# Transmit_module.net
KiCad netlist of a schematic drawn in EAGLE
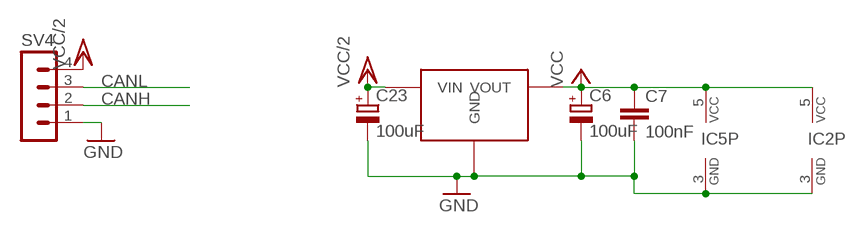
[diagram p0: schematic, sheet 1]
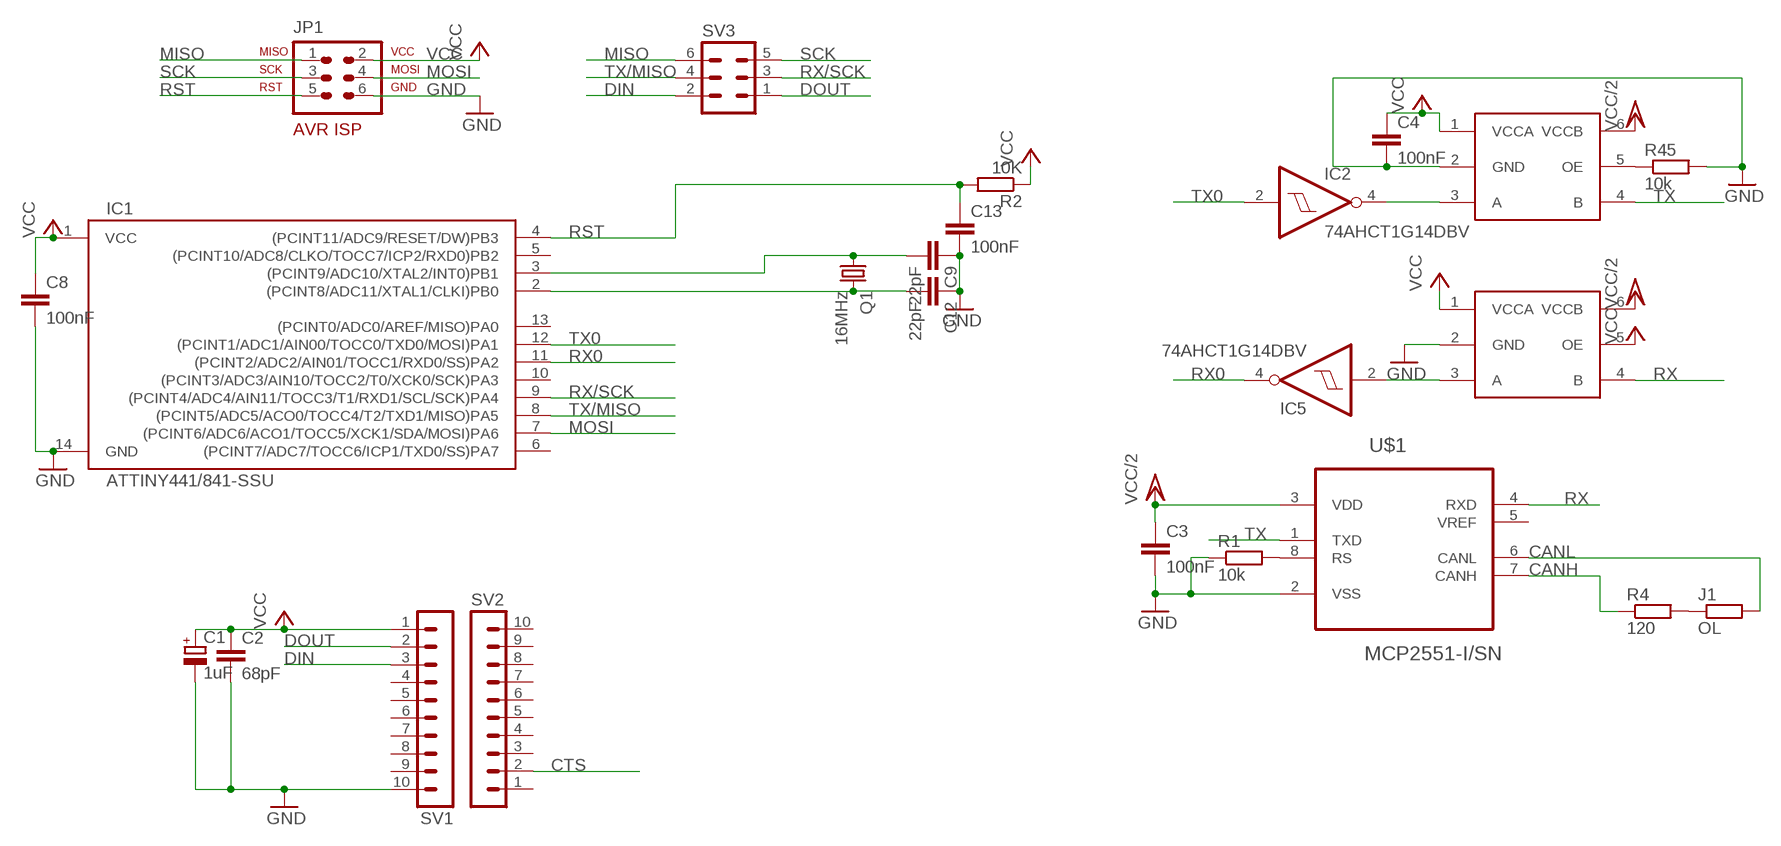
[diagram p1: schematic, sheet 2]

(export (version "E")
  (design (tool "Eeschema 10.0.6"))
  (components
    (comp (ref "C6")
      (value "100uF")
      (footprint "eagle-import:153CLV-0605")
      (libsource (lib "eagle-import") (part "CPOL-EU153CLV-0605"))
    )
    (comp (ref "C7")
      (value "100nF")
      (footprint "eagle-import:C0805")
      (libsource (lib "eagle-import") (part "C-EUC0805"))
    )
    (comp (ref "C23")
      (value "100uF")
      (footprint "eagle-import:153CLV-0605")
      (libsource (lib "eagle-import") (part "CPOL-EU153CLV-0605"))
    )
    (comp (ref "IC2")
      (value "74AHCT1G14DBV")
      (footprint "eagle-import:SOT23-5")
      (libsource (lib "eagle-import") (part "741G14DBVAHCT"))
    )
    (comp (ref "IC5")
      (value "74AHCT1G14DBV")
      (footprint "eagle-import:SOT23-5")
      (libsource (lib "eagle-import") (part "741G14DBVAHCT"))
    )
    (comp (ref "SV4")
      (value "MA04-1")
      (footprint "eagle-import:MA04-1")
      (libsource (lib "eagle-import") (part "MA04-1"))
    )
    (comp (ref "U$2")
      (value "TS2940")
      (footprint "eagle-import:TO-252")
      (libsource (lib "eagle-import") (part "TS2940"))
    )
    (comp (ref "C1")
      (value "1uF")
      (footprint "eagle-import:153CLV-0505")
      (libsource (lib "eagle-import") (part "CPOL-EU153CLV-0505"))
    )
    (comp (ref "C2")
      (value "68pF")
      (footprint "eagle-import:C0805")
      (libsource (lib "eagle-import") (part "C-EUC0805"))
    )
    (comp (ref "C3")
      (value "100nF")
      (footprint "eagle-import:C0805")
      (libsource (lib "eagle-import") (part "C-EUC0805"))
    )
    (comp (ref "C4")
      (value "100nF")
      (footprint "eagle-import:C0805")
      (libsource (lib "eagle-import") (part "C-EUC0805"))
    )
    (comp (ref "C8")
      (value "100nF")
      (footprint "eagle-import:C0805")
      (libsource (lib "eagle-import") (part "C-EUC0805"))
    )
    (comp (ref "C9")
      (value "22pF")
      (footprint "eagle-import:C0805")
      (libsource (lib "eagle-import") (part "C-EUC0805"))
    )
    (comp (ref "C12")
      (value "22pF")
      (footprint "eagle-import:C0805")
      (libsource (lib "eagle-import") (part "C-EUC0805"))
    )
    (comp (ref "C13")
      (value "100nF")
      (footprint "eagle-import:C0805")
      (libsource (lib "eagle-import") (part "C-EUC0805"))
    )
    (comp (ref "IC1")
      (value "ATTINY441/841-SSU")
      (footprint "eagle-import:SOIC14N")
      (libsource (lib "eagle-import") (part "ATTINY441/841-SSU"))
    )
    (comp (ref "J1")
      (value "OL")
      (footprint "eagle-import:R0805")
      (libsource (lib "eagle-import") (part "R-EU_R0805"))
    )
    (comp (ref "JP1")
      (value "AVR-ISP-6VERT")
      (footprint "eagle-import:AVR-ISP-6")
      (libsource (lib "eagle-import") (part "AVR-ISP-6VERT"))
    )
    (comp (ref "Q1")
      (value "16MHz")
      (footprint "eagle-import:HC49UP")
      (libsource (lib "eagle-import") (part "CRYSTALHC49UP"))
    )
    (comp (ref "R1")
      (value "10k")
      (footprint "eagle-import:M0805")
      (libsource (lib "eagle-import") (part "resistor_R-EU_M0805"))
    )
    (comp (ref "R2")
      (value "10K")
      (footprint "eagle-import:R0805")
      (libsource (lib "eagle-import") (part "R-EU_R0805"))
    )
    (comp (ref "R4")
      (value "120")
      (footprint "eagle-import:R0805")
      (libsource (lib "eagle-import") (part "R-EU_R0805"))
    )
    (comp (ref "R45")
      (value "10k")
      (footprint "eagle-import:R0805")
      (libsource (lib "eagle-import") (part "R-EU_R0805"))
    )
    (comp (ref "SV1")
      (value "MA10-1")
      (footprint "eagle-import:MA10-1")
      (libsource (lib "eagle-import") (part "MA10-1"))
    )
    (comp (ref "SV2")
      (value "MA10-1")
      (footprint "eagle-import:MA10-1")
      (libsource (lib "eagle-import") (part "MA10-1"))
    )
    (comp (ref "SV3")
      (value "MA03-2")
      (footprint "eagle-import:MA03-2")
      (libsource (lib "eagle-import") (part "MA03-2"))
    )
    (comp (ref "U$1")
      (value "MCP2551-I/SN")
      (footprint "eagle-import:SOIC127P600X175-8N")
      (libsource (lib "eagle-import") (part "MCP2551-I/SN"))
    )
    (comp (ref "U$3")
      (value "TXB0101")
      (footprint "eagle-import:TSOT23-6_DDC")
      (libsource (lib "eagle-import") (part "TXB0101"))
    )
    (comp (ref "U$4")
      (value "TXB0101")
      (footprint "eagle-import:TSOT23-6_DDC")
      (libsource (lib "eagle-import") (part "TXB0101"))
    )
  )
  (nets
    (net (code "1") (name "CANH") (class "Default")
      (node (ref "R4") (pin "1") (pinfunction "1_1") (pintype "passive"))
      (node (ref "SV4") (pin "2") (pinfunction "2_2") (pintype "passive"))
      (node (ref "U$1") (pin "7") (pinfunction "CANH_7") (pintype "bidirectional"))
    )
    (net (code "2") (name "CANL") (class "Default")
      (node (ref "J1") (pin "2") (pinfunction "2_2") (pintype "passive"))
      (node (ref "SV4") (pin "3") (pinfunction "3_3") (pintype "passive"))
      (node (ref "U$1") (pin "6") (pinfunction "CANL_6") (pintype "bidirectional"))
    )
    (net (code "3") (name "CTS") (class "Default")
      (node (ref "SV2") (pin "2") (pinfunction "2_2") (pintype "passive"))
    )
    (net (code "4") (name "DIN") (class "Default")
      (node (ref "SV1") (pin "3") (pinfunction "3_3") (pintype "passive"))
      (node (ref "SV3") (pin "2") (pinfunction "2_2") (pintype "passive"))
    )
    (net (code "5") (name "DOUT") (class "Default")
      (node (ref "SV1") (pin "2") (pinfunction "2_2") (pintype "passive"))
      (node (ref "SV3") (pin "1") (pinfunction "1_1") (pintype "passive"))
    )
    (net (code "6") (name "GND") (class "Default")
      (node (ref "C1") (pin "-") (pinfunction "-_-") (pintype "passive"))
      (node (ref "C12") (pin "1") (pinfunction "1_1") (pintype "passive"))
      (node (ref "C13") (pin "2") (pinfunction "2_2") (pintype "passive"))
      (node (ref "C2") (pin "2") (pinfunction "2_2") (pintype "passive"))
      (node (ref "C23") (pin "-") (pinfunction "-_-") (pintype "passive"))
      (node (ref "C3") (pin "2") (pinfunction "2_2") (pintype "passive"))
      (node (ref "C4") (pin "2") (pinfunction "2_2") (pintype "passive"))
      (node (ref "C6") (pin "-") (pinfunction "-_-") (pintype "passive"))
      (node (ref "C7") (pin "2") (pinfunction "2_2") (pintype "passive"))
      (node (ref "C8") (pin "2") (pinfunction "2_2") (pintype "passive"))
      (node (ref "C9") (pin "1") (pinfunction "1_1") (pintype "passive"))
      (node (ref "IC1") (pin "14") (pinfunction "GND_14") (pintype "bidirectional"))
      (node (ref "IC2") (pin "3") (pinfunction "GND_3") (pintype "power_in"))
      (node (ref "IC5") (pin "3") (pinfunction "GND_3") (pintype "power_in"))
      (node (ref "JP1") (pin "6") (pinfunction "6_6") (pintype "passive"))
      (node (ref "R1") (pin "1") (pinfunction "1_1") (pintype "passive"))
      (node (ref "R45") (pin "2") (pinfunction "2_2") (pintype "passive"))
      (node (ref "SV1") (pin "10") (pinfunction "10_10") (pintype "passive"))
      (node (ref "SV4") (pin "1") (pinfunction "1_1") (pintype "passive"))
      (node (ref "U$1") (pin "2") (pinfunction "VSS_2") (pintype "passive"))
      (node (ref "U$2") (pin "GND") (pinfunction "GND_GND") (pintype "bidirectional"))
      (node (ref "U$3") (pin "2") (pinfunction "GND_2") (pintype "power_in"))
      (node (ref "U$4") (pin "2") (pinfunction "GND_2") (pintype "power_in"))
    )
    (net (code "7") (name "MISO") (class "Default")
      (node (ref "JP1") (pin "1") (pinfunction "1_1") (pintype "passive"))
      (node (ref "SV3") (pin "6") (pinfunction "6_6") (pintype "passive"))
    )
    (net (code "8") (name "MOSI") (class "Default")
      (node (ref "IC1") (pin "7") (pinfunction "(PCINT6/ADC6/ACO1/TOCC5/XCK1/SDA/MOSI)PA6_7") (pintype "bidirectional"))
      (node (ref "JP1") (pin "4") (pinfunction "4_4") (pintype "passive"))
    )
    (net (code "9") (name "Net-(IC1-(PCINT8{slash}ADC11{slash}XTAL1{slash}CLKI)PB0)") (class "Default")
      (node (ref "C12") (pin "2") (pinfunction "2_2") (pintype "passive"))
      (node (ref "IC1") (pin "2") (pinfunction "(PCINT8/ADC11/XTAL1/CLKI)PB0_2") (pintype "bidirectional"))
      (node (ref "Q1") (pin "2") (pinfunction "2_2") (pintype "passive"))
    )
    (net (code "10") (name "Net-(IC1-(PCINT9{slash}ADC10{slash}XTAL2{slash}INT0)PB1)") (class "Default")
      (node (ref "C9") (pin "2") (pinfunction "2_2") (pintype "passive"))
      (node (ref "IC1") (pin "3") (pinfunction "(PCINT9/ADC10/XTAL2/INT0)PB1_3") (pintype "bidirectional"))
      (node (ref "Q1") (pin "1") (pinfunction "1_1") (pintype "passive"))
    )
    (net (code "11") (name "Net-(IC2A-O)") (class "Default")
      (node (ref "IC2") (pin "4") (pinfunction "O_4") (pintype "output"))
      (node (ref "U$3") (pin "3") (pinfunction "A_3") (pintype "bidirectional"))
    )
    (net (code "12") (name "Net-(IC5A-I)") (class "Default")
      (node (ref "IC5") (pin "2") (pinfunction "I_2") (pintype "input"))
      (node (ref "U$4") (pin "3") (pinfunction "A_3") (pintype "bidirectional"))
    )
    (net (code "13") (name "Net-(J1-Pad1)") (class "Default")
      (node (ref "J1") (pin "1") (pinfunction "1_1") (pintype "passive"))
      (node (ref "R4") (pin "2") (pinfunction "2_2") (pintype "passive"))
    )
    (net (code "14") (name "Net-(U$1-RS)") (class "Default")
      (node (ref "R1") (pin "2") (pinfunction "2_2") (pintype "passive"))
      (node (ref "U$1") (pin "8") (pinfunction "RS_8") (pintype "input"))
    )
    (net (code "15") (name "Net-(U$3-OE)") (class "Default")
      (node (ref "R45") (pin "1") (pinfunction "1_1") (pintype "passive"))
      (node (ref "U$3") (pin "5") (pinfunction "OE_5") (pintype "bidirectional"))
    )
    (net (code "16") (name "RST") (class "Default")
      (node (ref "C13") (pin "1") (pinfunction "1_1") (pintype "passive"))
      (node (ref "IC1") (pin "4") (pinfunction "(PCINT11/ADC9/RESET/DW)PB3_4") (pintype "bidirectional"))
      (node (ref "JP1") (pin "5") (pinfunction "5_5") (pintype "passive"))
      (node (ref "R2") (pin "2") (pinfunction "2_2") (pintype "passive"))
    )
    (net (code "17") (name "RX") (class "Default")
      (node (ref "U$1") (pin "4") (pinfunction "RXD_4") (pintype "output"))
      (node (ref "U$4") (pin "4") (pinfunction "B_4") (pintype "bidirectional"))
    )
    (net (code "18") (name "RX0") (class "Default")
      (node (ref "IC1") (pin "11") (pinfunction "(PCINT2/ADC2/AIN01/TOCC1/RXD0/SS)PA2_11") (pintype "bidirectional"))
      (node (ref "IC5") (pin "4") (pinfunction "O_4") (pintype "output"))
    )
    (net (code "19") (name "RX{slash}SCK") (class "Default")
      (node (ref "IC1") (pin "9") (pinfunction "(PCINT4/ADC4/AIN11/TOCC3/T1/RXD1/SCL/SCK)PA4_9") (pintype "bidirectional"))
      (node (ref "SV3") (pin "3") (pinfunction "3_3") (pintype "passive"))
    )
    (net (code "20") (name "SCK") (class "Default")
      (node (ref "JP1") (pin "3") (pinfunction "3_3") (pintype "passive"))
      (node (ref "SV3") (pin "5") (pinfunction "5_5") (pintype "passive"))
    )
    (net (code "21") (name "TX") (class "Default")
      (node (ref "U$1") (pin "1") (pinfunction "TXD_1") (pintype "input"))
      (node (ref "U$3") (pin "4") (pinfunction "B_4") (pintype "bidirectional"))
    )
    (net (code "22") (name "TX0") (class "Default")
      (node (ref "IC1") (pin "12") (pinfunction "(PCINT1/ADC1/AIN00/TOCC0/TXD0/MOSI)PA1_12") (pintype "bidirectional"))
      (node (ref "IC2") (pin "2") (pinfunction "I_2") (pintype "input"))
    )
    (net (code "23") (name "TX{slash}MISO") (class "Default")
      (node (ref "IC1") (pin "8") (pinfunction "(PCINT5/ADC5/ACO0/TOCC4/T2/TXD1/MISO)PA5_8") (pintype "bidirectional"))
      (node (ref "SV3") (pin "4") (pinfunction "4_4") (pintype "passive"))
    )
    (net (code "24") (name "VCC") (class "Default")
      (node (ref "C1") (pin "+") (pinfunction "+_+") (pintype "passive"))
      (node (ref "C2") (pin "1") (pinfunction "1_1") (pintype "passive"))
      (node (ref "C4") (pin "1") (pinfunction "1_1") (pintype "passive"))
      (node (ref "C6") (pin "+") (pinfunction "+_+") (pintype "passive"))
      (node (ref "C7") (pin "1") (pinfunction "1_1") (pintype "passive"))
      (node (ref "C8") (pin "1") (pinfunction "1_1") (pintype "passive"))
      (node (ref "IC1") (pin "1") (pinfunction "VCC_1") (pintype "bidirectional"))
      (node (ref "IC2") (pin "5") (pinfunction "VCC_5") (pintype "power_in"))
      (node (ref "IC5") (pin "5") (pinfunction "VCC_5") (pintype "power_in"))
      (node (ref "JP1") (pin "2") (pinfunction "2_2") (pintype "passive"))
      (node (ref "R2") (pin "1") (pinfunction "1_1") (pintype "passive"))
      (node (ref "SV1") (pin "1") (pinfunction "1_1") (pintype "passive"))
      (node (ref "U$2") (pin "VOUT") (pinfunction "VOUT_VOUT") (pintype "bidirectional"))
      (node (ref "U$3") (pin "1") (pinfunction "VCCA_1") (pintype "power_in"))
      (node (ref "U$4") (pin "1") (pinfunction "VCCA_1") (pintype "power_in"))
      (node (ref "U$4") (pin "5") (pinfunction "OE_5") (pintype "bidirectional"))
    )
    (net (code "25") (name "VCC{slash}2") (class "Default")
      (node (ref "C23") (pin "+") (pinfunction "+_+") (pintype "passive"))
      (node (ref "C3") (pin "1") (pinfunction "1_1") (pintype "passive"))
      (node (ref "SV4") (pin "4") (pinfunction "4_4") (pintype "passive"))
      (node (ref "U$1") (pin "3") (pinfunction "VDD_3") (pintype "power_in"))
      (node (ref "U$2") (pin "VIN") (pinfunction "VIN_VIN") (pintype "bidirectional"))
      (node (ref "U$3") (pin "6") (pinfunction "VCCB_6") (pintype "power_in"))
      (node (ref "U$4") (pin "6") (pinfunction "VCCB_6") (pintype "power_in"))
    )
    (net (code "26") (name "unconnected-(IC1-(PCINT0{slash}ADC0{slash}AREF{slash}MISO)PA0-Pad13)") (class "Default")
      (node (ref "IC1") (pin "13") (pinfunction "(PCINT0/ADC0/AREF/MISO)PA0_13") (pintype "bidirectional"))
    )
    (net (code "27") (name "unconnected-(IC1-(PCINT3{slash}ADC3{slash}AIN10{slash}TOCC2{slash}T0{slash}XCK0{slash}SCK)PA3-Pad10)") (class "Default")
      (node (ref "IC1") (pin "10") (pinfunction "(PCINT3/ADC3/AIN10/TOCC2/T0/XCK0/SCK)PA3_10") (pintype "bidirectional"))
    )
    (net (code "28") (name "unconnected-(IC1-(PCINT7{slash}ADC7{slash}TOCC6{slash}ICP1{slash}TXD0{slash}SS)PA7-Pad6)") (class "Default")
      (node (ref "IC1") (pin "6") (pinfunction "(PCINT7/ADC7/TOCC6/ICP1/TXD0/SS)PA7_6") (pintype "bidirectional"))
    )
    (net (code "29") (name "unconnected-(IC1-(PCINT10{slash}ADC8{slash}CLKO{slash}TOCC7{slash}ICP2{slash}RXD0)PB2-Pad5)") (class "Default")
      (node (ref "IC1") (pin "5") (pinfunction "(PCINT10/ADC8/CLKO/TOCC7/ICP2/RXD0)PB2_5") (pintype "bidirectional"))
    )
    (net (code "30") (name "unconnected-(SV1-Pad4)") (class "Default")
      (node (ref "SV1") (pin "4") (pinfunction "4_4") (pintype "passive"))
    )
    (net (code "31") (name "unconnected-(SV1-Pad5)") (class "Default")
      (node (ref "SV1") (pin "5") (pinfunction "5_5") (pintype "passive"))
    )
    (net (code "32") (name "unconnected-(SV1-Pad6)") (class "Default")
      (node (ref "SV1") (pin "6") (pinfunction "6_6") (pintype "passive"))
    )
    (net (code "33") (name "unconnected-(SV1-Pad7)") (class "Default")
      (node (ref "SV1") (pin "7") (pinfunction "7_7") (pintype "passive"))
    )
    (net (code "34") (name "unconnected-(SV1-Pad8)") (class "Default")
      (node (ref "SV1") (pin "8") (pinfunction "8_8") (pintype "passive"))
    )
    (net (code "35") (name "unconnected-(SV1-Pad9)") (class "Default")
      (node (ref "SV1") (pin "9") (pinfunction "9_9") (pintype "passive"))
    )
    (net (code "36") (name "unconnected-(SV2-Pad1)") (class "Default")
      (node (ref "SV2") (pin "1") (pinfunction "1_1") (pintype "passive"))
    )
    (net (code "37") (name "unconnected-(SV2-Pad3)") (class "Default")
      (node (ref "SV2") (pin "3") (pinfunction "3_3") (pintype "passive"))
    )
    (net (code "38") (name "unconnected-(SV2-Pad4)") (class "Default")
      (node (ref "SV2") (pin "4") (pinfunction "4_4") (pintype "passive"))
    )
    (net (code "39") (name "unconnected-(SV2-Pad5)") (class "Default")
      (node (ref "SV2") (pin "5") (pinfunction "5_5") (pintype "passive"))
    )
    (net (code "40") (name "unconnected-(SV2-Pad6)") (class "Default")
      (node (ref "SV2") (pin "6") (pinfunction "6_6") (pintype "passive"))
    )
    (net (code "41") (name "unconnected-(SV2-Pad7)") (class "Default")
      (node (ref "SV2") (pin "7") (pinfunction "7_7") (pintype "passive"))
    )
    (net (code "42") (name "unconnected-(SV2-Pad8)") (class "Default")
      (node (ref "SV2") (pin "8") (pinfunction "8_8") (pintype "passive"))
    )
    (net (code "43") (name "unconnected-(SV2-Pad9)") (class "Default")
      (node (ref "SV2") (pin "9") (pinfunction "9_9") (pintype "passive"))
    )
    (net (code "44") (name "unconnected-(SV2-Pad10)") (class "Default")
      (node (ref "SV2") (pin "10") (pinfunction "10_10") (pintype "passive"))
    )
    (net (code "45") (name "unconnected-(U$1-VREF-Pad5)") (class "Default")
      (node (ref "U$1") (pin "5") (pinfunction "VREF_5") (pintype "output"))
    )
  )
)
